# 8266_mpu.net
KiCad netlist of a schematic drawn in EAGLE
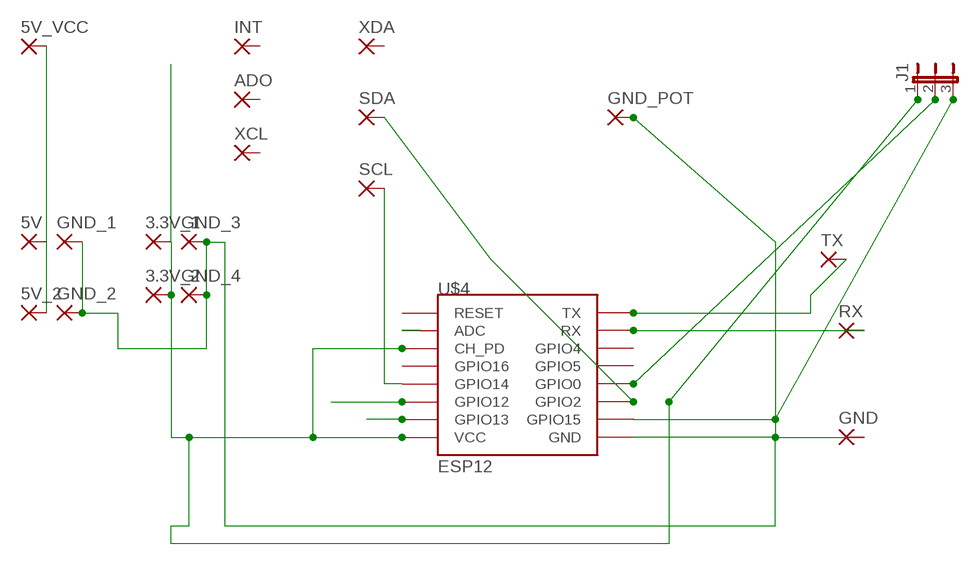
[diagram p0: schematic, sheet 1]

(export (version "E")
  (design (tool "Eeschema 10.0.6"))
  (components
    (comp (ref "3.3V_1")
      (value "2,15/1,0")
      (footprint "eagle-import:2,15_1,0")
      (libsource (lib "eagle-import") (part "2,15/1,0"))
    )
    (comp (ref "3.3V_2")
      (value "2,15/1,0")
      (footprint "eagle-import:2,15_1,0")
      (libsource (lib "eagle-import") (part "2,15/1,0"))
    )
    (comp (ref "5V")
      (value "2,15/1,0")
      (footprint "eagle-import:2,15_1,0")
      (libsource (lib "eagle-import") (part "2,15/1,0"))
    )
    (comp (ref "5V_2")
      (value "2,15/1,0")
      (footprint "eagle-import:2,15_1,0")
      (libsource (lib "eagle-import") (part "2,15/1,0"))
    )
    (comp (ref "5V_VCC")
      (value "2,15/1,0")
      (footprint "eagle-import:2,15_1,0")
      (libsource (lib "eagle-import") (part "2,15/1,0"))
    )
    (comp (ref "ADO")
      (value "2,15/1,0")
      (footprint "eagle-import:2,15_1,0")
      (libsource (lib "eagle-import") (part "2,15/1,0"))
    )
    (comp (ref "GND")
      (value "2,15/1,0")
      (footprint "eagle-import:2,15_1,0")
      (libsource (lib "eagle-import") (part "2,15/1,0"))
    )
    (comp (ref "GND_1")
      (value "2,15/1,0")
      (footprint "eagle-import:2,15_1,0")
      (libsource (lib "eagle-import") (part "2,15/1,0"))
    )
    (comp (ref "GND_2")
      (value "2,15/1,0")
      (footprint "eagle-import:2,15_1,0")
      (libsource (lib "eagle-import") (part "2,15/1,0"))
    )
    (comp (ref "GND_3")
      (value "2,15/1,0")
      (footprint "eagle-import:2,15_1,0")
      (libsource (lib "eagle-import") (part "2,15/1,0"))
    )
    (comp (ref "GND_4")
      (value "2,15/1,0")
      (footprint "eagle-import:2,15_1,0")
      (libsource (lib "eagle-import") (part "2,15/1,0"))
    )
    (comp (ref "GND_POT")
      (value "2,15/1,0")
      (footprint "eagle-import:2,15_1,0")
      (libsource (lib "eagle-import") (part "2,15/1,0"))
    )
    (comp (ref "INT")
      (value "2,15/1,0")
      (footprint "eagle-import:2,15_1,0")
      (libsource (lib "eagle-import") (part "2,15/1,0"))
    )
    (comp (ref "J1")
      (value "JP2E")
      (footprint "eagle-import:JP2")
      (libsource (lib "eagle-import") (part "JP2E"))
    )
    (comp (ref "RX")
      (value "2,15/1,0")
      (footprint "eagle-import:2,15_1,0")
      (libsource (lib "eagle-import") (part "2,15/1,0"))
    )
    (comp (ref "SCL")
      (value "2,15/1,0")
      (footprint "eagle-import:2,15_1,0")
      (libsource (lib "eagle-import") (part "2,15/1,0"))
    )
    (comp (ref "SDA")
      (value "2,15/1,0")
      (footprint "eagle-import:2,15_1,0")
      (libsource (lib "eagle-import") (part "2,15/1,0"))
    )
    (comp (ref "TX")
      (value "2,15/1,0")
      (footprint "eagle-import:2,15_1,0")
      (libsource (lib "eagle-import") (part "2,15/1,0"))
    )
    (comp (ref "U$4")
      (value "ESP12")
      (footprint "eagle-import:ESP12")
      (libsource (lib "eagle-import") (part "ESP12"))
    )
    (comp (ref "XCL")
      (value "2,15/1,0")
      (footprint "eagle-import:2,15_1,0")
      (libsource (lib "eagle-import") (part "2,15/1,0"))
    )
    (comp (ref "XDA")
      (value "2,15/1,0")
      (footprint "eagle-import:2,15_1,0")
      (libsource (lib "eagle-import") (part "2,15/1,0"))
    )
  )
  (nets
    (net (code "1") (name "/5V") (class "Default")
      (node (ref "5V") (pin "1") (pinfunction "P_1") (pintype "passive"))
      (node (ref "5V_2") (pin "1") (pinfunction "P_1") (pintype "passive"))
      (node (ref "5V_VCC") (pin "1") (pinfunction "P_1") (pintype "passive"))
      (node (ref "GND") (pin "1") (pinfunction "P_1") (pintype "passive"))
      (node (ref "GND_1") (pin "1") (pinfunction "P_1") (pintype "passive"))
      (node (ref "GND_2") (pin "1") (pinfunction "P_1") (pintype "passive"))
      (node (ref "GND_3") (pin "1") (pinfunction "P_1") (pintype "passive"))
      (node (ref "GND_4") (pin "1") (pinfunction "P_1") (pintype "passive"))
      (node (ref "GND_POT") (pin "1") (pinfunction "P_1") (pintype "passive"))
      (node (ref "J1") (pin "3") (pinfunction "3_3") (pintype "passive"))
      (node (ref "U$4") (pin "GND") (pinfunction "GND_GND") (pintype "bidirectional"))
      (node (ref "U$4") (pin "GPIO15") (pinfunction "GPIO15_GPIO15") (pintype "bidirectional"))
    )
    (net (code "2") (name "Net-(3.3V_1-P)") (class "Default")
      (node (ref "3.3V_1") (pin "1") (pinfunction "P_1") (pintype "passive"))
      (node (ref "3.3V_2") (pin "1") (pinfunction "P_1") (pintype "passive"))
      (node (ref "J1") (pin "1") (pinfunction "1_1") (pintype "passive"))
      (node (ref "U$4") (pin "CH_PD") (pinfunction "CH_PD_CH_PD") (pintype "bidirectional"))
      (node (ref "U$4") (pin "VCC") (pinfunction "VCC_VCC") (pintype "bidirectional"))
    )
    (net (code "3") (name "Net-(J1-Pad2)") (class "Default")
      (node (ref "J1") (pin "2") (pinfunction "2_2") (pintype "passive"))
      (node (ref "U$4") (pin "GPIO0") (pinfunction "GPIO0_GPIO0") (pintype "bidirectional"))
    )
    (net (code "4") (name "Net-(RX-P)") (class "Default")
      (node (ref "RX") (pin "1") (pinfunction "P_1") (pintype "passive"))
      (node (ref "U$4") (pin "RX") (pinfunction "RX_RX") (pintype "bidirectional"))
    )
    (net (code "5") (name "Net-(SCL-P)") (class "Default")
      (node (ref "SCL") (pin "1") (pinfunction "P_1") (pintype "passive"))
      (node (ref "U$4") (pin "GPIO14") (pinfunction "GPIO14_GPIO14") (pintype "bidirectional"))
    )
    (net (code "6") (name "Net-(SDA-P)") (class "Default")
      (node (ref "SDA") (pin "1") (pinfunction "P_1") (pintype "passive"))
      (node (ref "U$4") (pin "GPIO2") (pinfunction "GPIO2_GPIO2") (pintype "bidirectional"))
    )
    (net (code "7") (name "Net-(TX-P)") (class "Default")
      (node (ref "TX") (pin "1") (pinfunction "P_1") (pintype "passive"))
      (node (ref "U$4") (pin "TX") (pinfunction "TX_TX") (pintype "bidirectional"))
    )
    (net (code "8") (name "unconnected-(ADO-P-Pad1)") (class "Default")
      (node (ref "ADO") (pin "1") (pinfunction "P_1") (pintype "passive"))
    )
    (net (code "9") (name "unconnected-(INT-P-Pad1)") (class "Default")
      (node (ref "INT") (pin "1") (pinfunction "P_1") (pintype "passive"))
    )
    (net (code "10") (name "unconnected-(U$4-PadADC)") (class "Default")
      (node (ref "U$4") (pin "ADC") (pinfunction "ADC_ADC") (pintype "bidirectional"))
    )
    (net (code "11") (name "unconnected-(U$4-PadGPIO4)") (class "Default")
      (node (ref "U$4") (pin "GPIO4") (pinfunction "GPIO4_GPIO4") (pintype "bidirectional"))
    )
    (net (code "12") (name "unconnected-(U$4-PadGPIO5)") (class "Default")
      (node (ref "U$4") (pin "GPIO5") (pinfunction "GPIO5_GPIO5") (pintype "bidirectional"))
    )
    (net (code "13") (name "unconnected-(U$4-PadGPIO12)") (class "Default")
      (node (ref "U$4") (pin "GPIO12") (pinfunction "GPIO12_GPIO12") (pintype "bidirectional"))
    )
    (net (code "14") (name "unconnected-(U$4-PadGPIO13)") (class "Default")
      (node (ref "U$4") (pin "GPIO13") (pinfunction "GPIO13_GPIO13") (pintype "bidirectional"))
    )
    (net (code "15") (name "unconnected-(U$4-PadGPIO16)") (class "Default")
      (node (ref "U$4") (pin "GPIO16") (pinfunction "GPIO16_GPIO16") (pintype "bidirectional"))
    )
    (net (code "16") (name "unconnected-(U$4-PadRESET)") (class "Default")
      (node (ref "U$4") (pin "RESET") (pinfunction "RESET_RESET") (pintype "bidirectional"))
    )
    (net (code "17") (name "unconnected-(XCL-P-Pad1)") (class "Default")
      (node (ref "XCL") (pin "1") (pinfunction "P_1") (pintype "passive"))
    )
    (net (code "18") (name "unconnected-(XDA-P-Pad1)") (class "Default")
      (node (ref "XDA") (pin "1") (pinfunction "P_1") (pintype "passive"))
    )
  )
)
